# LCD_Display_encoder-1U.net
KiCad netlist of a schematic drawn in EAGLE
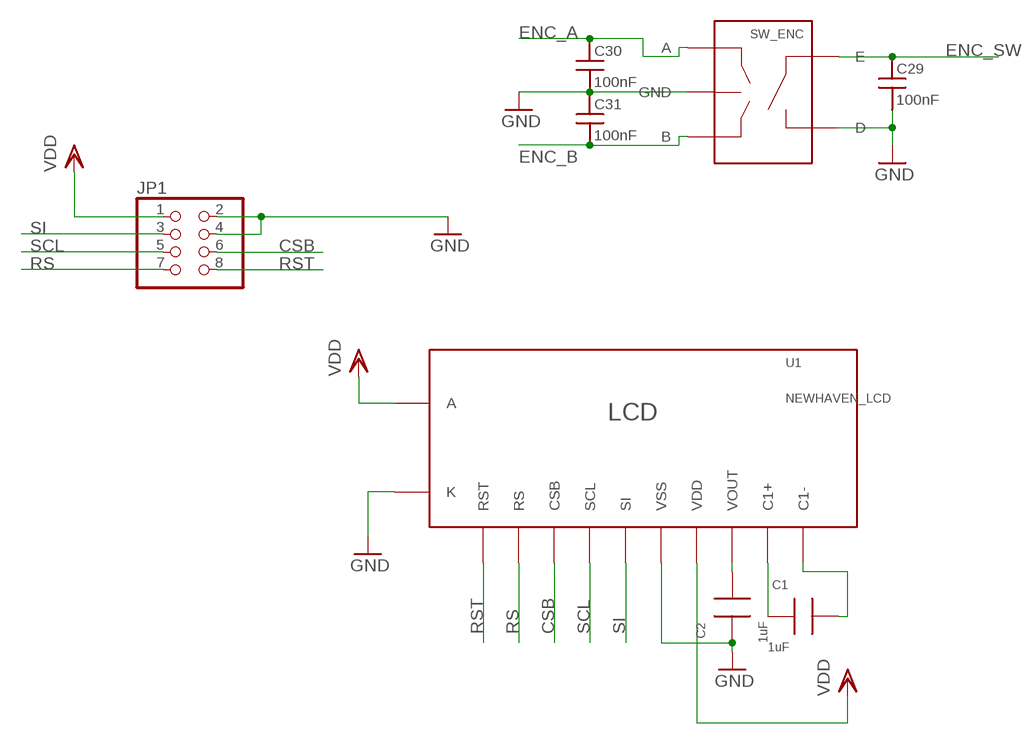
[diagram p0: schematic, sheet 1]

(export (version "E")
  (design (tool "Eeschema 10.0.6"))
  (components
    (comp (ref "C1")
      (value "1uF")
      (footprint "eagle-import:0805")
      (fields (field (name "PARTNO") "1276-2396-1-ND"))
      (libsource (lib "eagle-import") (part "CAP0805"))
    )
    (comp (ref "C2")
      (value "1uF")
      (footprint "eagle-import:0805")
      (fields (field (name "PARTNO") "1276-2396-1-ND"))
      (libsource (lib "eagle-import") (part "CAP0805"))
    )
    (comp (ref "C29")
      (value "100nF")
      (footprint "eagle-import:C_MLCC_0603")
      (fields (field (name "PARTNO") "1276-1936-1-ND"))
      (libsource (lib "eagle-import") (part "C_MLCC_SMDCMLCC_0603"))
    )
    (comp (ref "C30")
      (value "100nF")
      (footprint "eagle-import:C_MLCC_0603")
      (fields (field (name "PARTNO") "1276-1936-1-ND"))
      (libsource (lib "eagle-import") (part "C_MLCC_SMDCMLCC_0603"))
    )
    (comp (ref "C31")
      (value "100nF")
      (footprint "eagle-import:C_MLCC_0603")
      (fields (field (name "PARTNO") "1276-1936-1-ND"))
      (libsource (lib "eagle-import") (part "C_MLCC_SMDCMLCC_0603"))
    )
    (comp (ref "JP1")
      (value "PINHD-2X4SMT")
      (footprint "eagle-import:2X4SMT")
      (libsource (lib "eagle-import") (part "PINHD-2X4SMT"))
    )
    (comp (ref "SW_ENC")
      (value "ROTARY_PEC11R")
      (footprint "eagle-import:PEC11R")
      (fields (field (name "PARTNO") "PEC11R-4120F-S0018-ND"))
      (libsource (lib "eagle-import") (part "ROTARY_PEC11R"))
    )
    (comp (ref "U1")
      (value "NEWHAVEN_LCD")
      (footprint "eagle-import:NEWHAVEN_LCD")
      (fields (field (name "PARTNUM") "NHD-C0216CZ-FSW-FBW-3V3-ND"))
      (libsource (lib "eagle-import") (part "NEWHAVEN_LCD"))
    )
  )
  (nets
    (net (code "1") (name "/CSB") (class "Default")
      (node (ref "JP1") (pin "6") (pinfunction "6_6") (pintype "passive"))
      (node (ref "U1") (pin "3") (pinfunction "CSB_3") (pintype "bidirectional"))
    )
    (net (code "2") (name "/ENC_A") (class "Default")
      (node (ref "C30") (pin "P$1") (pinfunction "1_P$1") (pintype "passive"))
      (node (ref "SW_ENC") (pin "A") (pinfunction "A_A") (pintype "bidirectional"))
    )
    (net (code "3") (name "/ENC_B") (class "Default")
      (node (ref "C31") (pin "P$2") (pinfunction "2_P$2") (pintype "passive"))
      (node (ref "SW_ENC") (pin "B") (pinfunction "B_B") (pintype "bidirectional"))
    )
    (net (code "4") (name "/ENC_SW") (class "Default")
      (node (ref "C29") (pin "P$1") (pinfunction "1_P$1") (pintype "passive"))
      (node (ref "SW_ENC") (pin "2") (pinfunction "E_2") (pintype "bidirectional"))
    )
    (net (code "5") (name "/RS") (class "Default")
      (node (ref "JP1") (pin "7") (pinfunction "7_7") (pintype "passive"))
      (node (ref "U1") (pin "2") (pinfunction "RS_2") (pintype "bidirectional"))
    )
    (net (code "6") (name "/RST") (class "Default")
      (node (ref "JP1") (pin "8") (pinfunction "8_8") (pintype "passive"))
      (node (ref "U1") (pin "1") (pinfunction "RST_1") (pintype "bidirectional"))
    )
    (net (code "7") (name "/SCL") (class "Default")
      (node (ref "JP1") (pin "5") (pinfunction "5_5") (pintype "passive"))
      (node (ref "U1") (pin "4") (pinfunction "SCL_4") (pintype "bidirectional"))
    )
    (net (code "8") (name "/SI") (class "Default")
      (node (ref "JP1") (pin "3") (pinfunction "3_3") (pintype "passive"))
      (node (ref "U1") (pin "5") (pinfunction "SI_5") (pintype "bidirectional"))
    )
    (net (code "9") (name "GND") (class "Default")
      (node (ref "C2") (pin "1") (pinfunction "P$1_1") (pintype "passive"))
      (node (ref "C29") (pin "P$2") (pinfunction "2_P$2") (pintype "passive"))
      (node (ref "C30") (pin "P$2") (pinfunction "2_P$2") (pintype "passive"))
      (node (ref "C31") (pin "P$1") (pinfunction "1_P$1") (pintype "passive"))
      (node (ref "JP1") (pin "2") (pinfunction "2_2") (pintype "passive"))
      (node (ref "JP1") (pin "4") (pinfunction "4_4") (pintype "passive"))
      (node (ref "SW_ENC") (pin "1") (pinfunction "D_1") (pintype "bidirectional"))
      (node (ref "SW_ENC") (pin "C") (pinfunction "GND_C") (pintype "bidirectional"))
      (node (ref "U1") (pin "6") (pinfunction "VSS_6") (pintype "bidirectional"))
      (node (ref "U1") (pin "K") (pinfunction "K_K") (pintype "bidirectional"))
    )
    (net (code "10") (name "Net-(C1-P$1)") (class "Default")
      (node (ref "C1") (pin "1") (pinfunction "P$1_1") (pintype "passive"))
      (node (ref "U1") (pin "9") (pinfunction "C1+_9") (pintype "bidirectional"))
    )
    (net (code "11") (name "Net-(C1-P$2)") (class "Default")
      (node (ref "C1") (pin "2") (pinfunction "P$2_2") (pintype "passive"))
      (node (ref "U1") (pin "10") (pinfunction "C1-_10") (pintype "bidirectional"))
    )
    (net (code "12") (name "Net-(C2-P$2)") (class "Default")
      (node (ref "C2") (pin "2") (pinfunction "P$2_2") (pintype "passive"))
      (node (ref "U1") (pin "8") (pinfunction "VOUT_8") (pintype "bidirectional"))
    )
    (net (code "13") (name "VDD") (class "Default")
      (node (ref "JP1") (pin "1") (pinfunction "1_1") (pintype "passive"))
      (node (ref "U1") (pin "7") (pinfunction "VDD_7") (pintype "bidirectional"))
      (node (ref "U1") (pin "A") (pinfunction "A_A") (pintype "bidirectional"))
    )
  )
)
